# USB_OTG_FS.net
KiCad netlist of a schematic drawn in Altium Designer
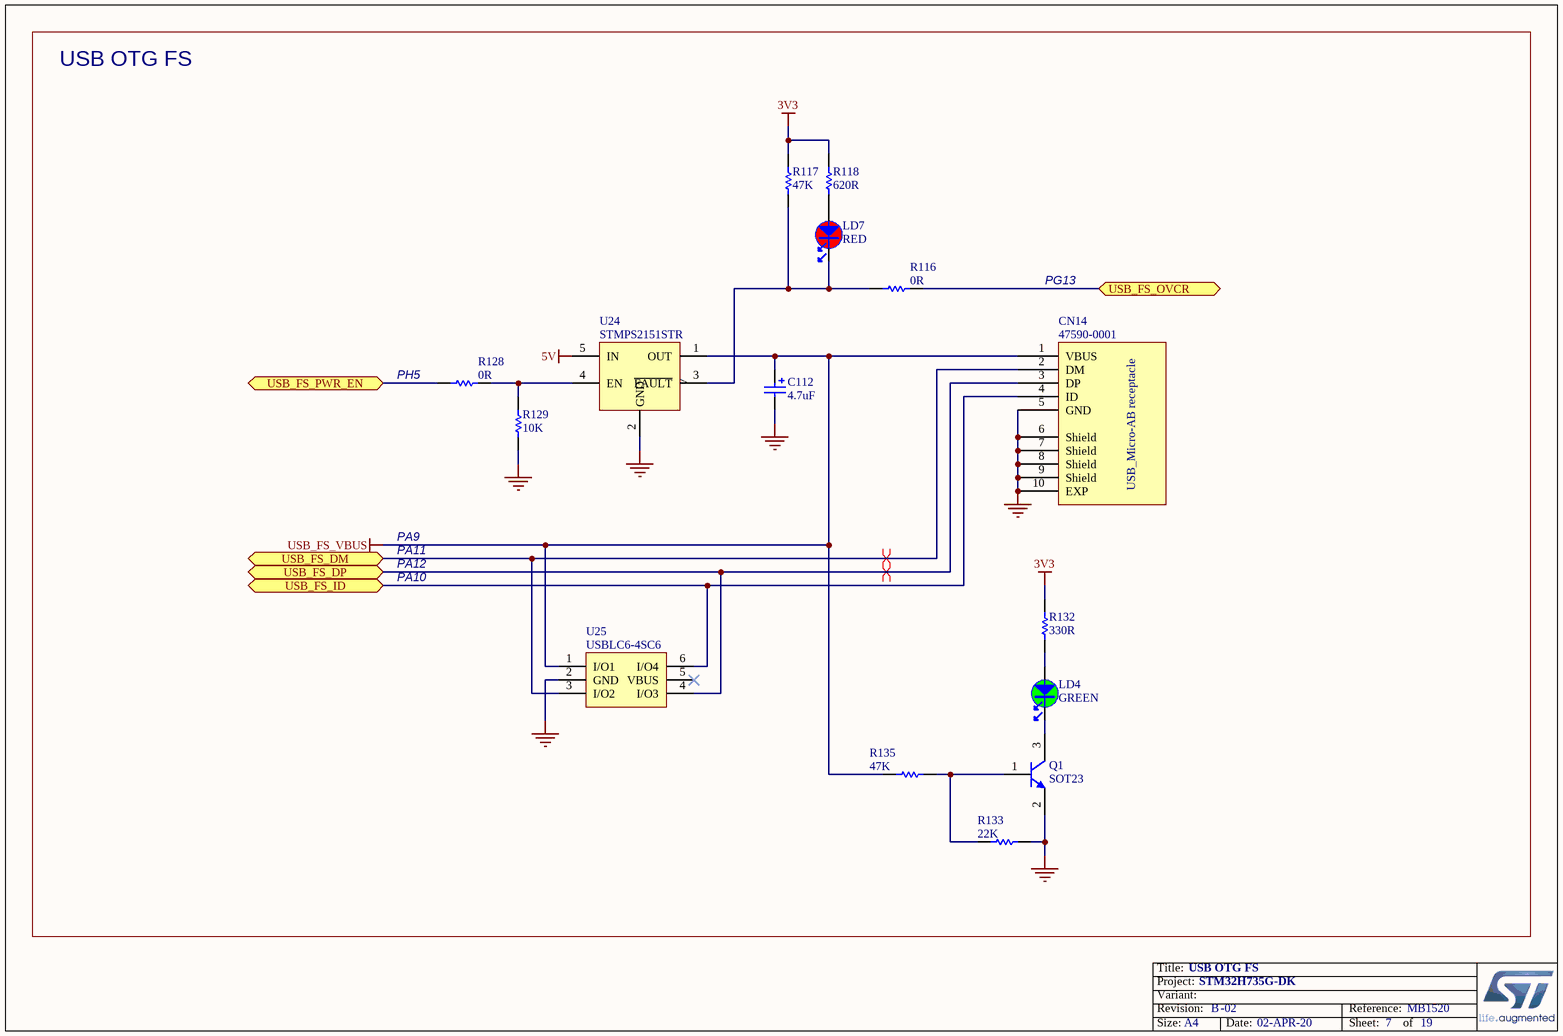
[diagram p0: USB OTG FS.SchDoc]

(export (version "E")
  (design (tool "Eeschema 10.0.6"))
  (components
    (comp (ref "C112")
      (value "4.7uF")
      (footprint "CPOL_VISHAY_TANTAL-595D_1407_H220")
      (description "Capacitor, Tantalum, 4.7uF, 16V, +/-10%, 595D case A")
      (fields
        (field (name "INTERNAL_PART_NUMBER") "MCD-00595")
        (field (name "MANUFACTURER_PART_NUMBER") "595D475X9016A2T")
        (field (name "PROVIDED_BY") "SUBCO")
      )
      (libsource (lib "MCD_PARTS_database") (part "Cap_POL_TANA"))
    )
    (comp (ref "CN14")
      (value "USB_uAB_47590.0001")
      (footprint "CON_USBMICROAB_MOLEX_47590-0001_H3")
      (description "USB-MICRO-AB, 0.65mm, RA, SMT, Top Mount (compatible with MCD-00661 USB certified)")
      (fields
        (field (name "INTERNAL_PART_NUMBER") "MCD-00022")
        (field (name "MANUFACTURER_PART_NUMBER") "47590-0001")
        (field (name "MANUFACTURER") "MOLEX")
        (field (name "PROVIDED_BY") "SUBCO")
      )
      (libsource (lib "MCD_PARTS_database") (part "USB_uAB_47590.0001"))
    )
    (comp (ref "LD4")
      (value "GREEN")
      (footprint "LED_0603_GREEN")
      (description "LED, Green, 0603")
      (fields
        (field (name "INTERNAL_PART_NUMBER") "MCD-00050")
        (field (name "MANUFACTURER_PART_NUMBER") "19-213SYGC/S530-E2/TR8")
        (field (name "PROVIDED_BY") "SUBCO")
      )
      (libsource (lib "MCD_PARTS_database") (part "LED_green"))
    )
    (comp (ref "LD7")
      (value "RED")
      (footprint "LED_0603_RED")
      (description "LED, Red, 0603")
      (fields
        (field (name "INTERNAL_PART_NUMBER") "MCD-00049")
        (field (name "MANUFACTURER_PART_NUMBER") "19-213-R6C-AP1Q2B/3T")
        (field (name "PROVIDED_BY") "SUBCO")
      )
      (libsource (lib "MCD_PARTS_database") (part "LED_red"))
    )
    (comp (ref "Q1")
      (value "SOT23")
      (footprint "NPN_SOT23")
      (description "NPN Bipolar Transistor")
      (fields
        (field (name "INTERNAL_PART_NUMBER") "MCD-00073")
        (field (name "MANUFACTURER_PART_NUMBER") "BSR14")
        (field (name "PROVIDED_BY") "SUBCO")
      )
      (libsource (lib "MCD_PARTS_database") (part "9013-SOT23"))
    )
    (comp (ref "R116")
      (value "0R")
      (footprint "R0402")
      (description "Resistor,0R,0402,5%,1/16W")
      (fields
        (field (name "INTERNAL_PART_NUMBER") "MCD-00052")
        (field (name "MANUFACTURER_PART_NUMBER") "RC0402JR-070RL")
        (field (name "PROVIDED_BY") "SUBCO")
      )
      (libsource (lib "MCD_PARTS_database") (part "Resistor"))
    )
    (comp (ref "R117")
      (value "47K")
      (footprint "R0402")
      (description "Resistor,47K,0402,1%,1/16W")
      (fields
        (field (name "INTERNAL_PART_NUMBER") "MCD-00063")
        (field (name "MANUFACTURER_PART_NUMBER") "RC0402FR-0747KL")
        (field (name "PROVIDED_BY") "SUBCO")
      )
      (libsource (lib "MCD_PARTS_database") (part "Resistor"))
    )
    (comp (ref "R118")
      (value "620R")
      (footprint "R0402")
      (description "Resistor,620R,0402,1%,1/16W")
      (fields
        (field (name "INTERNAL_PART_NUMBER") "MCD-00499")
        (field (name "MANUFACTURER_PART_NUMBER") "RC0402FR-07620RL")
        (field (name "PROVIDED_BY") "SUBCO")
      )
      (libsource (lib "MCD_PARTS_database") (part "Resistor"))
    )
    (comp (ref "R128")
      (value "0R")
      (footprint "R0402")
      (description "Resistor,0R,0402,5%,1/16W")
      (fields
        (field (name "INTERNAL_PART_NUMBER") "MCD-00052")
        (field (name "MANUFACTURER_PART_NUMBER") "RC0402JR-070RL")
        (field (name "PROVIDED_BY") "SUBCO")
      )
      (libsource (lib "MCD_PARTS_database") (part "Resistor"))
    )
    (comp (ref "R129")
      (value "10K")
      (footprint "R0402")
      (description "Resistor,10K,0402,1%,1/16W")
      (fields
        (field (name "INTERNAL_PART_NUMBER") "MCD-00053")
        (field (name "MANUFACTURER_PART_NUMBER") "RC0402FR-0710KL")
        (field (name "PROVIDED_BY") "SUBCO")
      )
      (libsource (lib "MCD_PARTS_database") (part "Resistor"))
    )
    (comp (ref "R132")
      (value "330R")
      (footprint "R0402")
      (description "Resistor,330R,0402,1%,1/16W")
      (fields
        (field (name "INTERNAL_PART_NUMBER") "MCD-00062")
        (field (name "MANUFACTURER_PART_NUMBER") "RC0402FR-07330RL")
        (field (name "PROVIDED_BY") "SUBCO")
      )
      (libsource (lib "MCD_PARTS_database") (part "Resistor"))
    )
    (comp (ref "R133")
      (value "22K")
      (footprint "R0402")
      (description "Resistor,22K,0402,1%,1/16W")
      (fields
        (field (name "INTERNAL_PART_NUMBER") "MCD-00429")
        (field (name "MANUFACTURER_PART_NUMBER") "RC0402FR-0722KL")
        (field (name "PROVIDED_BY") "SUBCO")
      )
      (libsource (lib "MCD_PARTS_database") (part "Resistor"))
    )
    (comp (ref "R135")
      (value "47K")
      (footprint "R0402")
      (description "Resistor,47K,0402,1%,1/16W")
      (fields
        (field (name "INTERNAL_PART_NUMBER") "MCD-00063")
        (field (name "MANUFACTURER_PART_NUMBER") "RC0402FR-0747KL")
        (field (name "PROVIDED_BY") "SUBCO")
      )
      (libsource (lib "MCD_PARTS_database") (part "Resistor"))
    )
    (comp (ref "U24")
      (value "STMPS2151STR")
      (footprint "MOS_SOT23-5L")
      (description "500mA, Enhanced single channel power switches with active high enable pin")
      (fields
        (field (name "INTERNAL_PART_NUMBER") "MCD-00159")
        (field (name "MANUFACTURER") "STMICROELECTRONICS")
        (field (name "PROVIDED_BY") "SUBCO with ST control")
      )
      (libsource (lib "MCD_PARTS_database") (part "STMPS2151STR"))
    )
    (comp (ref "U25")
      (value "USBLC6-4SC6")
      (footprint "ESD_SOT23-6L")
      (description "Very low capacitance ESD protection , 4 lines")
      (fields
        (field (name "INTERNAL_PART_NUMBER") "MCD-00250")
        (field (name "MANUFACTURER") "STMICROELECTRONICS")
        (field (name "PROVIDED_BY") "SUBCO with ST control")
      )
      (libsource (lib "MCD_PARTS_database") (part "USBLC6-4SC6"))
    )
  )
  (nets
    (net (code "1") (name "/USB_FS_DM") (class "Default")
      (node (ref "CN14") (pin "2") (pinfunction "DM_2") (pintype "passive"))
      (node (ref "U25") (pin "3") (pinfunction "I/O2_3") (pintype "passive"))
    )
    (net (code "2") (name "/USB_FS_DP") (class "Default")
      (node (ref "CN14") (pin "3") (pinfunction "DP_3") (pintype "passive"))
      (node (ref "U25") (pin "4") (pinfunction "I/O3_4") (pintype "passive"))
    )
    (net (code "3") (name "/USB_FS_ID") (class "Default")
      (node (ref "CN14") (pin "4") (pinfunction "ID_4") (pintype "passive"))
      (node (ref "U25") (pin "6") (pinfunction "I/O4_6") (pintype "passive"))
    )
    (net (code "4") (name "/USB_FS_OVCR") (class "Default")
      (node (ref "R116") (pin "2") (pinfunction "2_2") (pintype "passive"))
    )
    (net (code "5") (name "/USB_FS_PWR_EN") (class "Default")
      (node (ref "R128") (pin "1") (pinfunction "1_1") (pintype "passive"))
    )
    (net (code "6") (name "3V3") (class "Default")
      (node (ref "R117") (pin "2") (pinfunction "2_2") (pintype "passive"))
      (node (ref "R118") (pin "2") (pinfunction "2_2") (pintype "passive"))
      (node (ref "R132") (pin "2") (pinfunction "2_2") (pintype "passive"))
    )
    (net (code "7") (name "5V") (class "Default")
      (node (ref "U24") (pin "5") (pinfunction "IN_5") (pintype "passive"))
    )
    (net (code "8") (name "GND") (class "Default")
      (node (ref "C112") (pin "2") (pinfunction "2_2") (pintype "passive"))
      (node (ref "CN14") (pin "10") (pinfunction "EXP_10") (pintype "passive"))
      (node (ref "CN14") (pin "5") (pinfunction "GND_5") (pintype "passive"))
      (node (ref "CN14") (pin "6") (pinfunction "Shield_6") (pintype "passive"))
      (node (ref "CN14") (pin "7") (pinfunction "Shield_7") (pintype "passive"))
      (node (ref "CN14") (pin "8") (pinfunction "Shield_8") (pintype "passive"))
      (node (ref "CN14") (pin "9") (pinfunction "Shield_9") (pintype "passive"))
      (node (ref "Q1") (pin "2") (pinfunction "E_2") (pintype "passive"))
      (node (ref "R129") (pin "1") (pinfunction "1_1") (pintype "passive"))
      (node (ref "R133") (pin "2") (pinfunction "2_2") (pintype "passive"))
      (node (ref "U24") (pin "2") (pinfunction "GND_2") (pintype "passive"))
      (node (ref "U25") (pin "2") (pinfunction "GND_2") (pintype "passive"))
    )
    (net (code "9") (name "Net-(LD4-Pad1)") (class "Default")
      (node (ref "LD4") (pin "1") (pintype "passive"))
      (node (ref "R132") (pin "1") (pinfunction "1_1") (pintype "passive"))
    )
    (net (code "10") (name "Net-(LD7-Pad1)") (class "Default")
      (node (ref "LD7") (pin "1") (pintype "passive"))
      (node (ref "R118") (pin "1") (pinfunction "1_1") (pintype "passive"))
    )
    (net (code "11") (name "Net-(Q1-B)") (class "Default")
      (node (ref "Q1") (pin "1") (pinfunction "B_1") (pintype "passive"))
      (node (ref "R133") (pin "1") (pinfunction "1_1") (pintype "passive"))
      (node (ref "R135") (pin "1") (pinfunction "1_1") (pintype "passive"))
    )
    (net (code "12") (name "Net-(Q1-C)") (class "Default")
      (node (ref "LD4") (pin "2") (pintype "passive"))
      (node (ref "Q1") (pin "3") (pinfunction "C_3") (pintype "passive"))
    )
    (net (code "13") (name "Net-(U24-EN)") (class "Default")
      (node (ref "R128") (pin "2") (pinfunction "2_2") (pintype "passive"))
      (node (ref "R129") (pin "2") (pinfunction "2_2") (pintype "passive"))
      (node (ref "U24") (pin "4") (pinfunction "EN_4") (pintype "passive"))
    )
    (net (code "14") (name "Net-(U24-~{FAULT})") (class "Default")
      (node (ref "LD7") (pin "2") (pintype "passive"))
      (node (ref "R116") (pin "1") (pinfunction "1_1") (pintype "passive"))
      (node (ref "R117") (pin "1") (pinfunction "1_1") (pintype "passive"))
      (node (ref "U24") (pin "3") (pinfunction "~{FAULT}_3") (pintype "passive"))
    )
    (net (code "15") (name "USB_FS_VBUS") (class "Default")
      (node (ref "C112") (pin "1") (pinfunction "1_1") (pintype "passive"))
      (node (ref "CN14") (pin "1") (pinfunction "VBUS_1") (pintype "passive"))
      (node (ref "R135") (pin "2") (pinfunction "2_2") (pintype "passive"))
      (node (ref "U24") (pin "1") (pinfunction "OUT_1") (pintype "passive"))
      (node (ref "U25") (pin "1") (pinfunction "I/O1_1") (pintype "passive"))
    )
    (net (code "16") (name "unconnected-(U25-VBUS-Pad5)") (class "Default")
      (node (ref "U25") (pin "5") (pinfunction "VBUS_5") (pintype "passive+no_connect"))
    )
  )
)
